# macro_fader.net
KiCad netlist of a schematic drawn in EAGLE
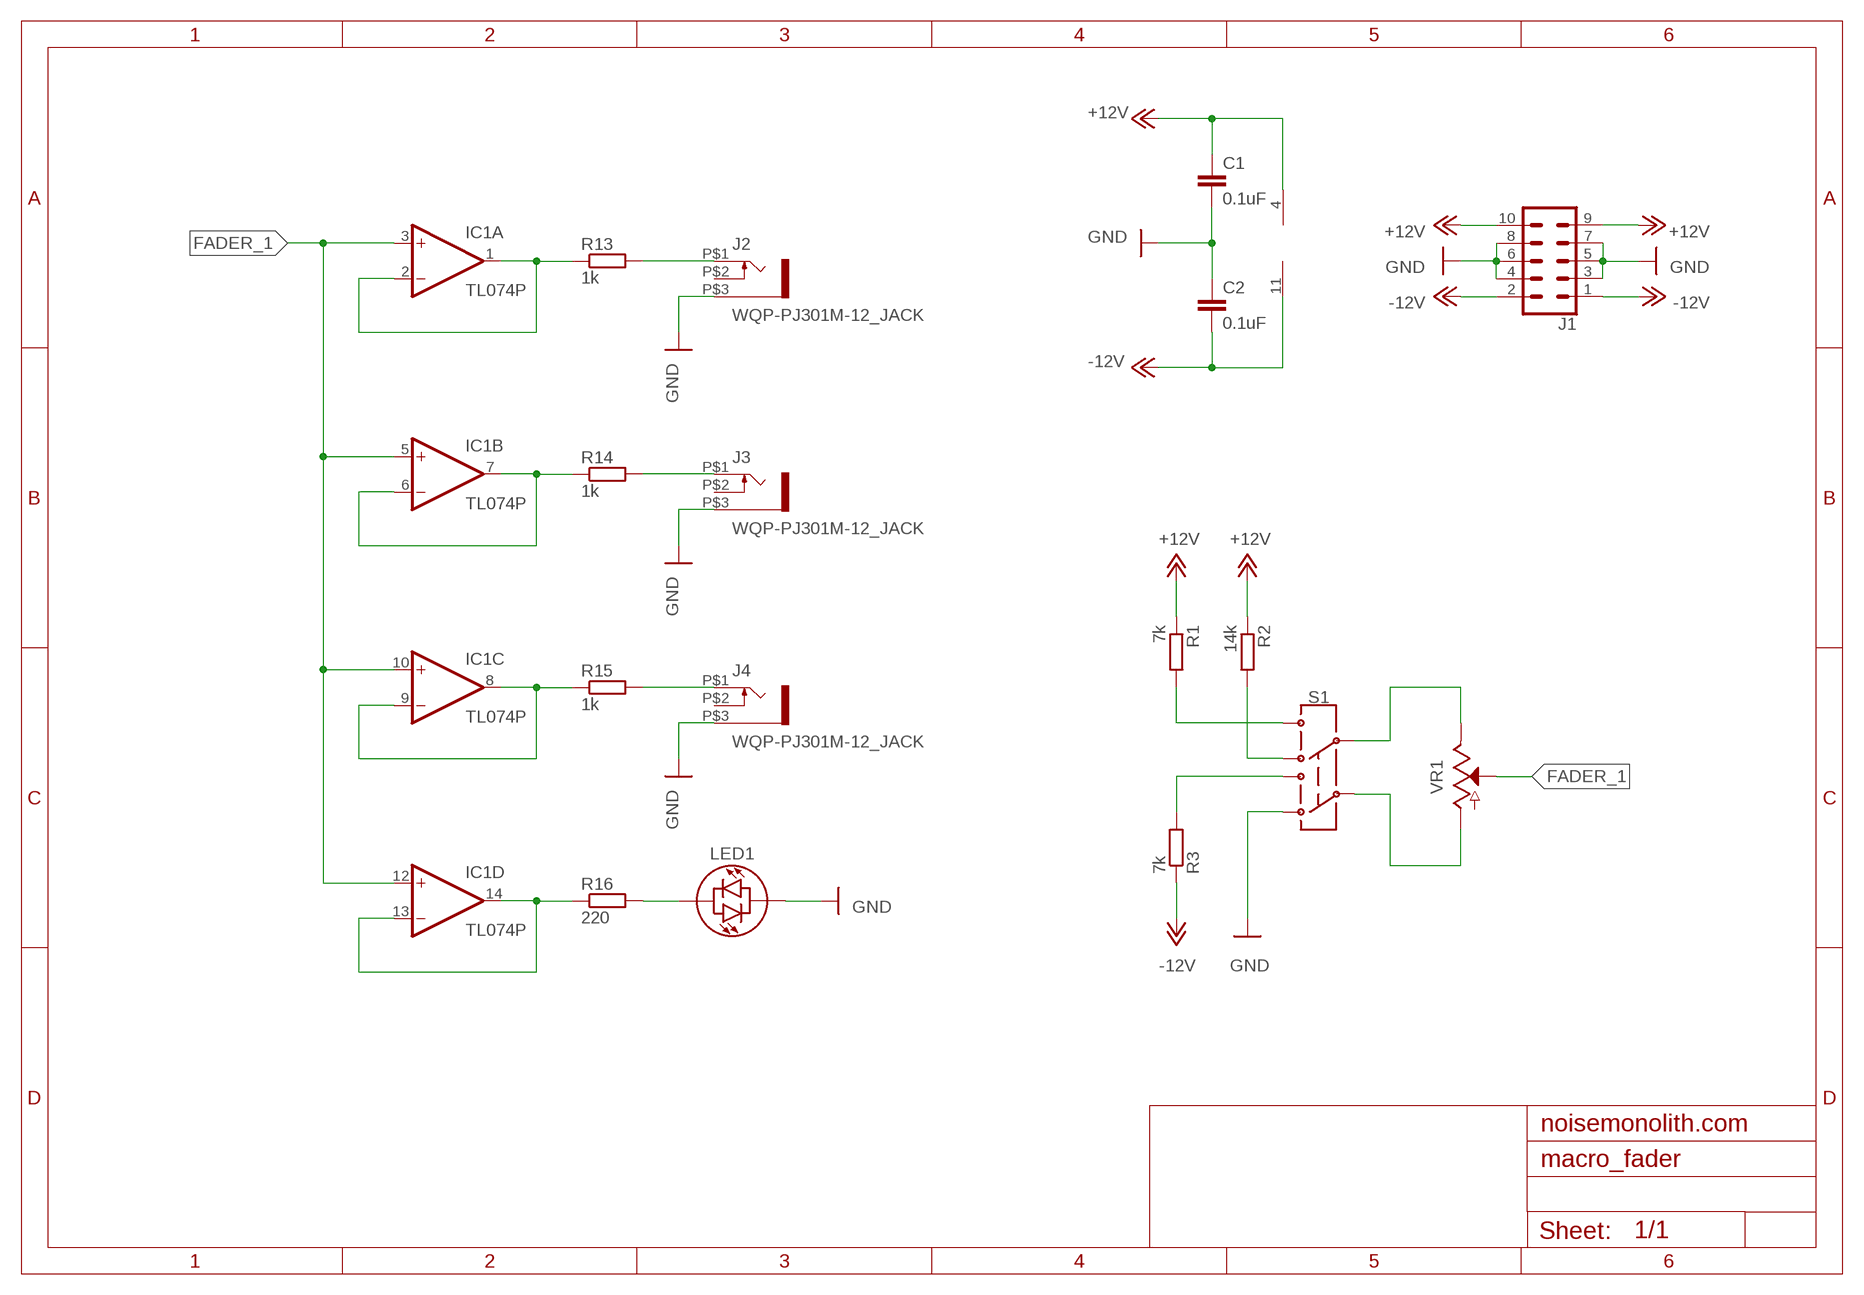
[diagram p0: schematic, sheet 1]

(export (version "E")
  (design (tool "Eeschema 10.0.6"))
  (components
    (comp (ref "C1")
      (value "0.1uF")
      (footprint "eagle-import:C050-025X075")
      (libsource (lib "eagle-import") (part "C-EU050-025X075"))
    )
    (comp (ref "C2")
      (value "0.1uF")
      (footprint "eagle-import:C050-025X075")
      (libsource (lib "eagle-import") (part "C-EU050-025X075"))
    )
    (comp (ref "IC1")
      (value "TL074P")
      (footprint "eagle-import:DIL14")
      (libsource (lib "eagle-import") (part "TL074P"))
    )
    (comp (ref "J1")
      (value "CONN_05X2SHD")
      (footprint "eagle-import:2X5-SHROUDED")
      (libsource (lib "eagle-import") (part "CONN_05X2SHD"))
    )
    (comp (ref "J2")
      (value "WQP-PJ301M-12_JACK")
      (footprint "eagle-import:WQP-PJ301M-12_JACK")
      (libsource (lib "eagle-import") (part "WQP-PJ301M-12_JACK"))
    )
    (comp (ref "J3")
      (value "WQP-PJ301M-12_JACK")
      (footprint "eagle-import:WQP-PJ301M-12_JACK")
      (libsource (lib "eagle-import") (part "WQP-PJ301M-12_JACK"))
    )
    (comp (ref "J4")
      (value "WQP-PJ301M-12_JACK")
      (footprint "eagle-import:WQP-PJ301M-12_JACK")
      (libsource (lib "eagle-import") (part "WQP-PJ301M-12_JACK"))
    )
    (comp (ref "LED1")
      (value "A-1076_RED-GREEN-LED-3MM3MM")
      (footprint "eagle-import:A-1076_RED-GREEN-LED-3MM")
      (libsource (lib "eagle-import") (part "A-1076_RED-GREEN-LED-3MM3MM"))
    )
    (comp (ref "R1")
      (value "7k")
      (footprint "eagle-import:0207_7")
      (libsource (lib "eagle-import") (part "R-EU_0207/7"))
    )
    (comp (ref "R2")
      (value "14k")
      (footprint "eagle-import:0207_7")
      (libsource (lib "eagle-import") (part "R-EU_0207/7"))
    )
    (comp (ref "R3")
      (value "7k")
      (footprint "eagle-import:0207_7")
      (libsource (lib "eagle-import") (part "R-EU_0207/7"))
    )
    (comp (ref "R13")
      (value "1k")
      (footprint "eagle-import:0207_7")
      (libsource (lib "eagle-import") (part "R-EU_0207/7"))
    )
    (comp (ref "R14")
      (value "1k")
      (footprint "eagle-import:0207_7")
      (libsource (lib "eagle-import") (part "R-EU_0207/7"))
    )
    (comp (ref "R15")
      (value "1k")
      (footprint "eagle-import:0207_7")
      (libsource (lib "eagle-import") (part "R-EU_0207/7"))
    )
    (comp (ref "R16")
      (value "220")
      (footprint "eagle-import:0207_7")
      (libsource (lib "eagle-import") (part "R-EU_0207/7"))
    )
    (comp (ref "S1")
      (value "A-4568_MINITOGGLESWITCH_DPDT_ON-ON")
      (footprint "eagle-import:A-4568_MINITOGGLESWITCH_DPDT_ON-ON")
      (libsource (lib "eagle-import") (part "A-4568_MINITOGGLESWITCH_DPDT_ON-ON"))
    )
    (comp (ref "VR1")
      (value "F4505-N0SC2B10K")
      (footprint "eagle-import:F4505-N0SC2B10K")
      (libsource (lib "eagle-import") (part "F4505-N0SC2B10K"))
    )
  )
  (nets
    (net (code "1") (name "+12V") (class "Default")
      (node (ref "C1") (pin "1") (pinfunction "1_1") (pintype "passive"))
      (node (ref "IC1") (pin "4") (pinfunction "V+_4") (pintype "power_in"))
      (node (ref "J1") (pin "10") (pinfunction "10_10") (pintype "passive"))
      (node (ref "J1") (pin "9") (pinfunction "9_9") (pintype "passive"))
      (node (ref "R1") (pin "1") (pinfunction "1_1") (pintype "passive"))
      (node (ref "R2") (pin "1") (pinfunction "1_1") (pintype "passive"))
    )
    (net (code "2") (name "-12V") (class "Default")
      (node (ref "C2") (pin "2") (pinfunction "2_2") (pintype "passive"))
      (node (ref "IC1") (pin "11") (pinfunction "V-_11") (pintype "power_in"))
      (node (ref "J1") (pin "1") (pinfunction "1_1") (pintype "passive"))
      (node (ref "J1") (pin "2") (pinfunction "2_2") (pintype "passive"))
      (node (ref "R3") (pin "1") (pinfunction "1_1") (pintype "passive"))
    )
    (net (code "3") (name "FADER_1") (class "Default")
      (node (ref "IC1") (pin "10") (pinfunction "+IN_10") (pintype "input"))
      (node (ref "IC1") (pin "12") (pinfunction "+IN_12") (pintype "input"))
      (node (ref "IC1") (pin "3") (pinfunction "+IN_3") (pintype "input"))
      (node (ref "IC1") (pin "5") (pinfunction "+IN_5") (pintype "input"))
      (node (ref "VR1") (pin "2") (pinfunction "2_2") (pintype "passive"))
    )
    (net (code "4") (name "GND") (class "Default")
      (node (ref "C1") (pin "2") (pinfunction "2_2") (pintype "passive"))
      (node (ref "C2") (pin "1") (pinfunction "1_1") (pintype "passive"))
      (node (ref "J1") (pin "3") (pinfunction "3_3") (pintype "passive"))
      (node (ref "J1") (pin "4") (pinfunction "4_4") (pintype "passive"))
      (node (ref "J1") (pin "5") (pinfunction "5_5") (pintype "passive"))
      (node (ref "J1") (pin "6") (pinfunction "6_6") (pintype "passive"))
      (node (ref "J1") (pin "7") (pinfunction "7_7") (pintype "passive"))
      (node (ref "J1") (pin "8") (pinfunction "8_8") (pintype "passive"))
      (node (ref "J2") (pin "P$3") (pinfunction "1_P$3") (pintype "passive"))
      (node (ref "J3") (pin "P$3") (pinfunction "1_P$3") (pintype "passive"))
      (node (ref "J4") (pin "P$3") (pinfunction "1_P$3") (pintype "passive"))
      (node (ref "LED1") (pin "G") (pinfunction "GREEN_G") (pintype "passive"))
      (node (ref "S1") (pin "6") (pinfunction "6_6") (pintype "bidirectional"))
    )
    (net (code "5") (name "Net-(IC1A--IN)") (class "Default")
      (node (ref "IC1") (pin "1") (pinfunction "OUT_1") (pintype "output"))
      (node (ref "IC1") (pin "2") (pinfunction "-IN_2") (pintype "input"))
      (node (ref "R13") (pin "1") (pinfunction "1_1") (pintype "passive"))
    )
    (net (code "6") (name "Net-(IC1B--IN)") (class "Default")
      (node (ref "IC1") (pin "6") (pinfunction "-IN_6") (pintype "input"))
      (node (ref "IC1") (pin "7") (pinfunction "OUT_7") (pintype "output"))
      (node (ref "R14") (pin "1") (pinfunction "1_1") (pintype "passive"))
    )
    (net (code "7") (name "Net-(IC1C--IN)") (class "Default")
      (node (ref "IC1") (pin "8") (pinfunction "OUT_8") (pintype "output"))
      (node (ref "IC1") (pin "9") (pinfunction "-IN_9") (pintype "input"))
      (node (ref "R15") (pin "1") (pinfunction "1_1") (pintype "passive"))
    )
    (net (code "8") (name "Net-(IC1D--IN)") (class "Default")
      (node (ref "IC1") (pin "13") (pinfunction "-IN_13") (pintype "input"))
      (node (ref "IC1") (pin "14") (pinfunction "OUT_14") (pintype "output"))
      (node (ref "R16") (pin "1") (pinfunction "1_1") (pintype "passive"))
    )
    (net (code "9") (name "Net-(J2-2)") (class "Default")
      (node (ref "J2") (pin "P$1") (pinfunction "2_P$1") (pintype "passive"))
      (node (ref "R13") (pin "2") (pinfunction "2_2") (pintype "passive"))
    )
    (net (code "10") (name "Net-(J3-2)") (class "Default")
      (node (ref "J3") (pin "P$1") (pinfunction "2_P$1") (pintype "passive"))
      (node (ref "R14") (pin "2") (pinfunction "2_2") (pintype "passive"))
    )
    (net (code "11") (name "Net-(J4-2)") (class "Default")
      (node (ref "J4") (pin "P$1") (pinfunction "2_P$1") (pintype "passive"))
      (node (ref "R15") (pin "2") (pinfunction "2_2") (pintype "passive"))
    )
    (net (code "12") (name "Net-(LED1-RED)") (class "Default")
      (node (ref "LED1") (pin "R") (pinfunction "RED_R") (pintype "passive"))
      (node (ref "R16") (pin "2") (pinfunction "2_2") (pintype "passive"))
    )
    (net (code "13") (name "Net-(R1-Pad2)") (class "Default")
      (node (ref "R1") (pin "2") (pinfunction "2_2") (pintype "passive"))
      (node (ref "S1") (pin "1") (pinfunction "1_1") (pintype "bidirectional"))
    )
    (net (code "14") (name "Net-(R2-Pad2)") (class "Default")
      (node (ref "R2") (pin "2") (pinfunction "2_2") (pintype "passive"))
      (node (ref "S1") (pin "3") (pinfunction "3_3") (pintype "bidirectional"))
    )
    (net (code "15") (name "Net-(R3-Pad2)") (class "Default")
      (node (ref "R3") (pin "2") (pinfunction "2_2") (pintype "passive"))
      (node (ref "S1") (pin "4") (pinfunction "4_4") (pintype "bidirectional"))
    )
    (net (code "16") (name "Net-(S1-Pad2)") (class "Default")
      (node (ref "S1") (pin "2") (pinfunction "2_2") (pintype "bidirectional"))
      (node (ref "VR1") (pin "1") (pinfunction "1_1") (pintype "passive"))
    )
    (net (code "17") (name "Net-(S1-Pad5)") (class "Default")
      (node (ref "S1") (pin "5") (pinfunction "5_5") (pintype "bidirectional"))
      (node (ref "VR1") (pin "3") (pinfunction "3_3") (pintype "passive"))
    )
    (net (code "18") (name "unconnected-(J2-3-PadP$2)") (class "Default")
      (node (ref "J2") (pin "P$2") (pinfunction "3_P$2") (pintype "passive"))
    )
    (net (code "19") (name "unconnected-(J3-3-PadP$2)") (class "Default")
      (node (ref "J3") (pin "P$2") (pinfunction "3_P$2") (pintype "passive"))
    )
    (net (code "20") (name "unconnected-(J4-3-PadP$2)") (class "Default")
      (node (ref "J4") (pin "P$2") (pinfunction "3_P$2") (pintype "passive"))
    )
  )
)
